# MicroSEQSheet.net
KiCad netlist of a schematic drawn in Altium Designer
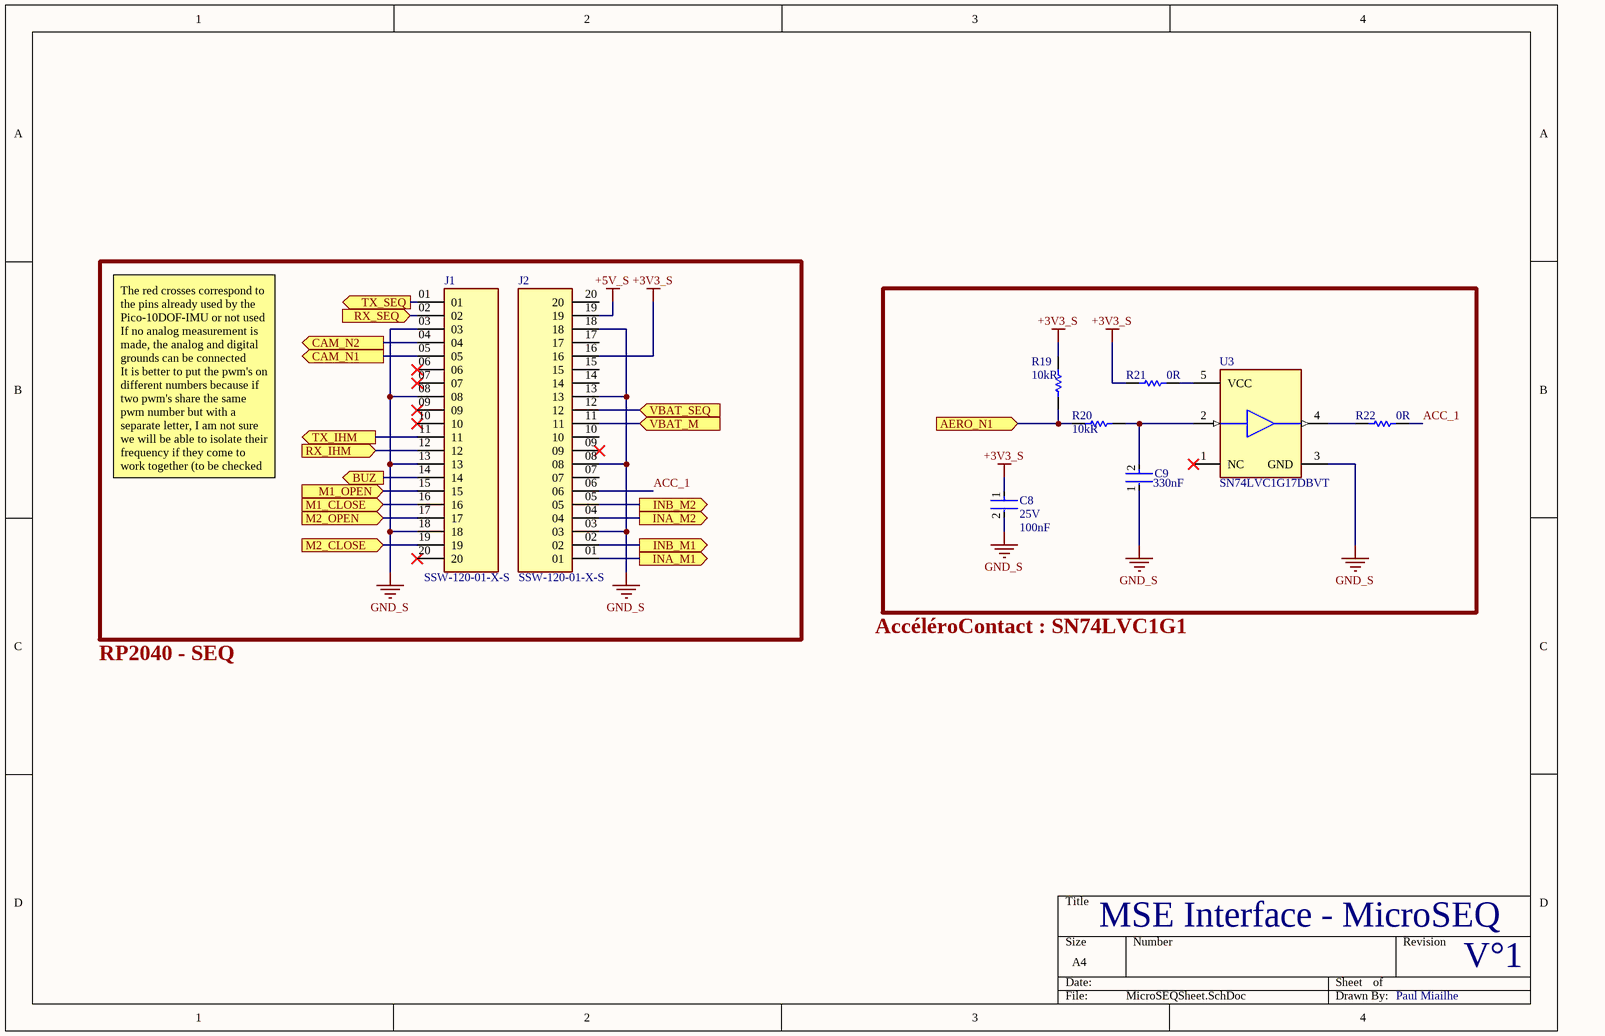
[diagram p0: MicroSEQSheet.SchDoc]

(export (version "E")
  (design (tool "Eeschema 10.0.6"))
  (components
    (comp (ref "C8")
      (value "CGA3E2X7R1E104K080AA")
      (footprint "FP-CGA3E-0_3-0_1-MFG")
      (description "Cap Ceramic 100nF 25V X7R 10% Pad SMD 0603 +125°C Automotive T/R")
      (fields
        (field (name "VOLTAGE RATING (DC)") "25V")
        (field (name "CAPACITANCE") "100nF")
        (field (name "TOLERANCE") "10%")
        (field (name "MANUFACTURER") "TDK")
      )
      (libsource (lib "Altium Content Vault") (part "b4654b650e69147ec39a6b967a45e02"))
    )
    (comp (ref "C9")
      (value "C1608X7R1H334K080AC")
      (footprint "FP-C1608-080-0_1-IPC_B")
      (description "Multilayer Ceramic Capacitors 330nF ±10% 50V X7R SMD 0603")
      (fields
        (field (name "CAPACITANCE") "330nF")
        (field (name "TOLERANCE") "10%")
        (field (name "VOLTAGE") "50V")
      )
      (libsource (lib "Altium Content Vault") (part "236180d848d6139a670b325ea6854c9"))
    )
    (comp (ref "J1")
      (value "SSW-120-01-X-S")
      (footprint "SAMTEC_SSW-120-01-X-S")
      (description "SSW - Samtec 2.54mm Single Row Straight Socket Strip 8.5 Profile - Fast Stock")
      (fields (field (name "MP") "SSW-120-01-G-S") (field (name "MF") "Samtec"))
      (libsource (lib "Saint-Étienne School of Mines- Mines Space") (part "SSW-120-01-X-S"))
    )
    (comp (ref "J2")
      (value "SSW-120-01-X-S")
      (footprint "SAMTEC_SSW-120-01-X-S")
      (description "SSW - Samtec 2.54mm Single Row Straight Socket Strip 8.5 Profile - Fast Stock")
      (fields (field (name "MP") "SSW-120-01-G-S") (field (name "MF") "Samtec"))
      (libsource (lib "") (part "SSW-120-01-X-S_1"))
    )
    (comp (ref "R19")
      (value "ERJ3EKF1002V")
      (footprint "RESC1609X55X30LL15T15")
      (description "Chip Resistor, 10 KOhm, +/- 1%, 0.1 W, -55 to 155 degC, 0603 (1608 Metric), RoHS, Tape and Reel")
      (fields
        (field (name "RESISTANCE") "10kR")
        (field (name "TOLERANCE") "1%")
        (field (name "MANUFACTURER") "Panasonic")
      )
      (libsource (lib "Altium Content Vault") (part "RES-2"))
    )
    (comp (ref "R20")
      (value "ERJ3EKF1002V")
      (footprint "RESC1609X55X30LL15T15")
      (description "Chip Resistor, 10 KOhm, +/- 1%, 0.1 W, -55 to 155 degC, 0603 (1608 Metric), RoHS, Tape and Reel")
      (fields
        (field (name "RESISTANCE") "10kR")
        (field (name "TOLERANCE") "1%")
        (field (name "MANUFACTURER") "Panasonic")
      )
      (libsource (lib "Altium Content Vault") (part "RES-2"))
    )
    (comp (ref "R21")
      (value "0R")
      (footprint "RESC1608X55X25ML10T15")
      (description "Chip Resistor, 0 Ohm, +/- 5%, 0.1 W, -55 to 155 degC, 0603 (1608 Metric), RoHS, Tape and Reel")
      (fields (field (name "TOLERANCE") "5%") (field (name "MANUFACTURER") "Yageo"))
      (libsource (lib "Altium Content Vault") (part "RES-2"))
    )
    (comp (ref "R22")
      (value "0R")
      (footprint "RESC1608X55X25ML10T15")
      (description "Chip Resistor, 0 Ohm, +/- 5%, 0.1 W, -55 to 155 degC, 0603 (1608 Metric), RoHS, Tape and Reel")
      (fields (field (name "TOLERANCE") "5%") (field (name "MANUFACTURER") "Yageo"))
      (libsource (lib "Altium Content Vault") (part "RES-2"))
    )
    (comp (ref "U3")
      (value "SN74LVC1G17DBVT")
      (footprint "FP-DBV0005A-MFG")
      (description "IC BUF NON-INVERT 5.5V SOT23-5")
      (fields
        (field (name "MANUFACTURER") "Texas Instruments")
        (field (name "OCTOPART") "https://octopart.com/sn74lvc1g17dbvt-texas+instruments-2326350")
      )
      (libsource (lib "Altium Content Vault") (part "d67d855942c6c6b24b3bb5c51ad1e18"))
    )
  )
  (nets
    (net (code "1") (name "+3V3_S") (class "Default")
      (node (ref "C8") (pin "1") (pinfunction "1_1") (pintype "passive"))
      (node (ref "J2") (pin "16") (pinfunction "16_16") (pintype "passive"))
      (node (ref "R19") (pin "2") (pinfunction "2_2") (pintype "passive"))
      (node (ref "R21") (pin "1") (pinfunction "1_1") (pintype "passive"))
    )
    (net (code "2") (name "+5V_S") (class "Default")
      (node (ref "J2") (pin "19") (pinfunction "19_19") (pintype "passive"))
    )
    (net (code "3") (name "/ACC_1") (class "Default")
      (node (ref "J2") (pin "06") (pinfunction "06_06") (pintype "passive"))
      (node (ref "R22") (pin "2") (pinfunction "2_2") (pintype "passive"))
    )
    (net (code "4") (name "/AERO_N1") (class "Default")
      (node (ref "R19") (pin "1") (pinfunction "1_1") (pintype "passive"))
      (node (ref "R20") (pin "2") (pinfunction "2_2") (pintype "passive"))
    )
    (net (code "5") (name "/BUZ") (class "Default")
      (node (ref "J1") (pin "14") (pinfunction "14_14") (pintype "passive"))
    )
    (net (code "6") (name "/CAM_N1") (class "Default")
      (node (ref "J1") (pin "05") (pinfunction "05_05") (pintype "passive"))
    )
    (net (code "7") (name "/CAM_N2") (class "Default")
      (node (ref "J1") (pin "04") (pinfunction "04_04") (pintype "passive"))
    )
    (net (code "8") (name "/INA_M1") (class "Default")
      (node (ref "J2") (pin "01") (pinfunction "01_01") (pintype "passive"))
    )
    (net (code "9") (name "/INA_M2") (class "Default")
      (node (ref "J2") (pin "04") (pinfunction "04_04") (pintype "passive"))
    )
    (net (code "10") (name "/INB_M1") (class "Default")
      (node (ref "J2") (pin "02") (pinfunction "02_02") (pintype "passive"))
    )
    (net (code "11") (name "/INB_M2") (class "Default")
      (node (ref "J2") (pin "05") (pinfunction "05_05") (pintype "passive"))
    )
    (net (code "12") (name "/M1_CLOSE") (class "Default")
      (node (ref "J1") (pin "16") (pinfunction "16_16") (pintype "passive"))
    )
    (net (code "13") (name "/M1_OPEN") (class "Default")
      (node (ref "J1") (pin "15") (pinfunction "15_15") (pintype "passive"))
    )
    (net (code "14") (name "/M2_CLOSE") (class "Default")
      (node (ref "J1") (pin "19") (pinfunction "19_19") (pintype "passive"))
    )
    (net (code "15") (name "/M2_OPEN") (class "Default")
      (node (ref "J1") (pin "17") (pinfunction "17_17") (pintype "passive"))
    )
    (net (code "16") (name "/RX_IHM") (class "Default")
      (node (ref "J1") (pin "12") (pinfunction "12_12") (pintype "passive"))
    )
    (net (code "17") (name "/RX_SEQ") (class "Default")
      (node (ref "J1") (pin "02") (pinfunction "02_02") (pintype "passive"))
    )
    (net (code "18") (name "/TX_IHM") (class "Default")
      (node (ref "J1") (pin "11") (pinfunction "11_11") (pintype "passive"))
    )
    (net (code "19") (name "/TX_SEQ") (class "Default")
      (node (ref "J1") (pin "01") (pinfunction "01_01") (pintype "passive"))
    )
    (net (code "20") (name "/VBAT_M") (class "Default")
      (node (ref "J2") (pin "11") (pinfunction "11_11") (pintype "passive"))
    )
    (net (code "21") (name "/VBAT_SEQ") (class "Default")
      (node (ref "J2") (pin "12") (pinfunction "12_12") (pintype "passive"))
    )
    (net (code "22") (name "GND_S") (class "Default")
      (node (ref "C8") (pin "2") (pinfunction "2_2") (pintype "passive"))
      (node (ref "C9") (pin "1") (pinfunction "1_1") (pintype "passive"))
      (node (ref "J1") (pin "03") (pinfunction "03_03") (pintype "passive"))
      (node (ref "J1") (pin "08") (pinfunction "08_08") (pintype "passive"))
      (node (ref "J1") (pin "13") (pinfunction "13_13") (pintype "passive"))
      (node (ref "J1") (pin "18") (pinfunction "18_18") (pintype "passive"))
      (node (ref "J2") (pin "03") (pinfunction "03_03") (pintype "passive"))
      (node (ref "J2") (pin "08") (pinfunction "08_08") (pintype "passive"))
      (node (ref "J2") (pin "13") (pinfunction "13_13") (pintype "passive"))
      (node (ref "J2") (pin "18") (pinfunction "18_18") (pintype "passive"))
      (node (ref "U3") (pin "3") (pinfunction "GND_3") (pintype "power_in"))
    )
    (net (code "23") (name "Net-(U3-A)") (class "Default")
      (node (ref "C9") (pin "2") (pinfunction "2_2") (pintype "passive"))
      (node (ref "R20") (pin "1") (pinfunction "1_1") (pintype "passive"))
      (node (ref "U3") (pin "2") (pinfunction "A_2") (pintype "input"))
    )
    (net (code "24") (name "Net-(U3-VCC)") (class "Default")
      (node (ref "R21") (pin "2") (pinfunction "2_2") (pintype "passive"))
      (node (ref "U3") (pin "5") (pinfunction "VCC_5") (pintype "power_in"))
    )
    (net (code "25") (name "Net-(U3-Y)") (class "Default")
      (node (ref "R22") (pin "1") (pinfunction "1_1") (pintype "passive"))
      (node (ref "U3") (pin "4") (pinfunction "Y_4") (pintype "output"))
    )
    (net (code "26") (name "unconnected-(J1-Pad06)") (class "Default")
      (node (ref "J1") (pin "06") (pinfunction "06_06") (pintype "passive+no_connect"))
    )
    (net (code "27") (name "unconnected-(J1-Pad07)") (class "Default")
      (node (ref "J1") (pin "07") (pinfunction "07_07") (pintype "passive+no_connect"))
    )
    (net (code "28") (name "unconnected-(J1-Pad09)") (class "Default")
      (node (ref "J1") (pin "09") (pinfunction "09_09") (pintype "passive+no_connect"))
    )
    (net (code "29") (name "unconnected-(J1-Pad10)") (class "Default")
      (node (ref "J1") (pin "10") (pinfunction "10_10") (pintype "passive+no_connect"))
    )
    (net (code "30") (name "unconnected-(J1-Pad20)") (class "Default")
      (node (ref "J1") (pin "20") (pinfunction "20_20") (pintype "passive+no_connect"))
    )
    (net (code "31") (name "unconnected-(J2-Pad07)") (class "Default")
      (node (ref "J2") (pin "07") (pinfunction "07_07") (pintype "passive"))
    )
    (net (code "32") (name "unconnected-(J2-Pad09)") (class "Default")
      (node (ref "J2") (pin "09") (pinfunction "09_09") (pintype "passive+no_connect"))
    )
    (net (code "33") (name "unconnected-(J2-Pad10)") (class "Default")
      (node (ref "J2") (pin "10") (pinfunction "10_10") (pintype "passive"))
    )
    (net (code "34") (name "unconnected-(J2-Pad14)") (class "Default")
      (node (ref "J2") (pin "14") (pinfunction "14_14") (pintype "passive"))
    )
    (net (code "35") (name "unconnected-(J2-Pad15)") (class "Default")
      (node (ref "J2") (pin "15") (pinfunction "15_15") (pintype "passive"))
    )
    (net (code "36") (name "unconnected-(J2-Pad17)") (class "Default")
      (node (ref "J2") (pin "17") (pinfunction "17_17") (pintype "passive"))
    )
    (net (code "37") (name "unconnected-(J2-Pad20)") (class "Default")
      (node (ref "J2") (pin "20") (pinfunction "20_20") (pintype "passive"))
    )
    (net (code "38") (name "unconnected-(U3-NC-Pad1)") (class "Default")
      (node (ref "U3") (pin "1") (pinfunction "NC_1") (pintype "passive+no_connect"))
    )
  )
)
